# ProPrj_ChopperIA_NoBuriedBlindVias.net
KiCad netlist of a schematic drawn in EasyEDA Pro
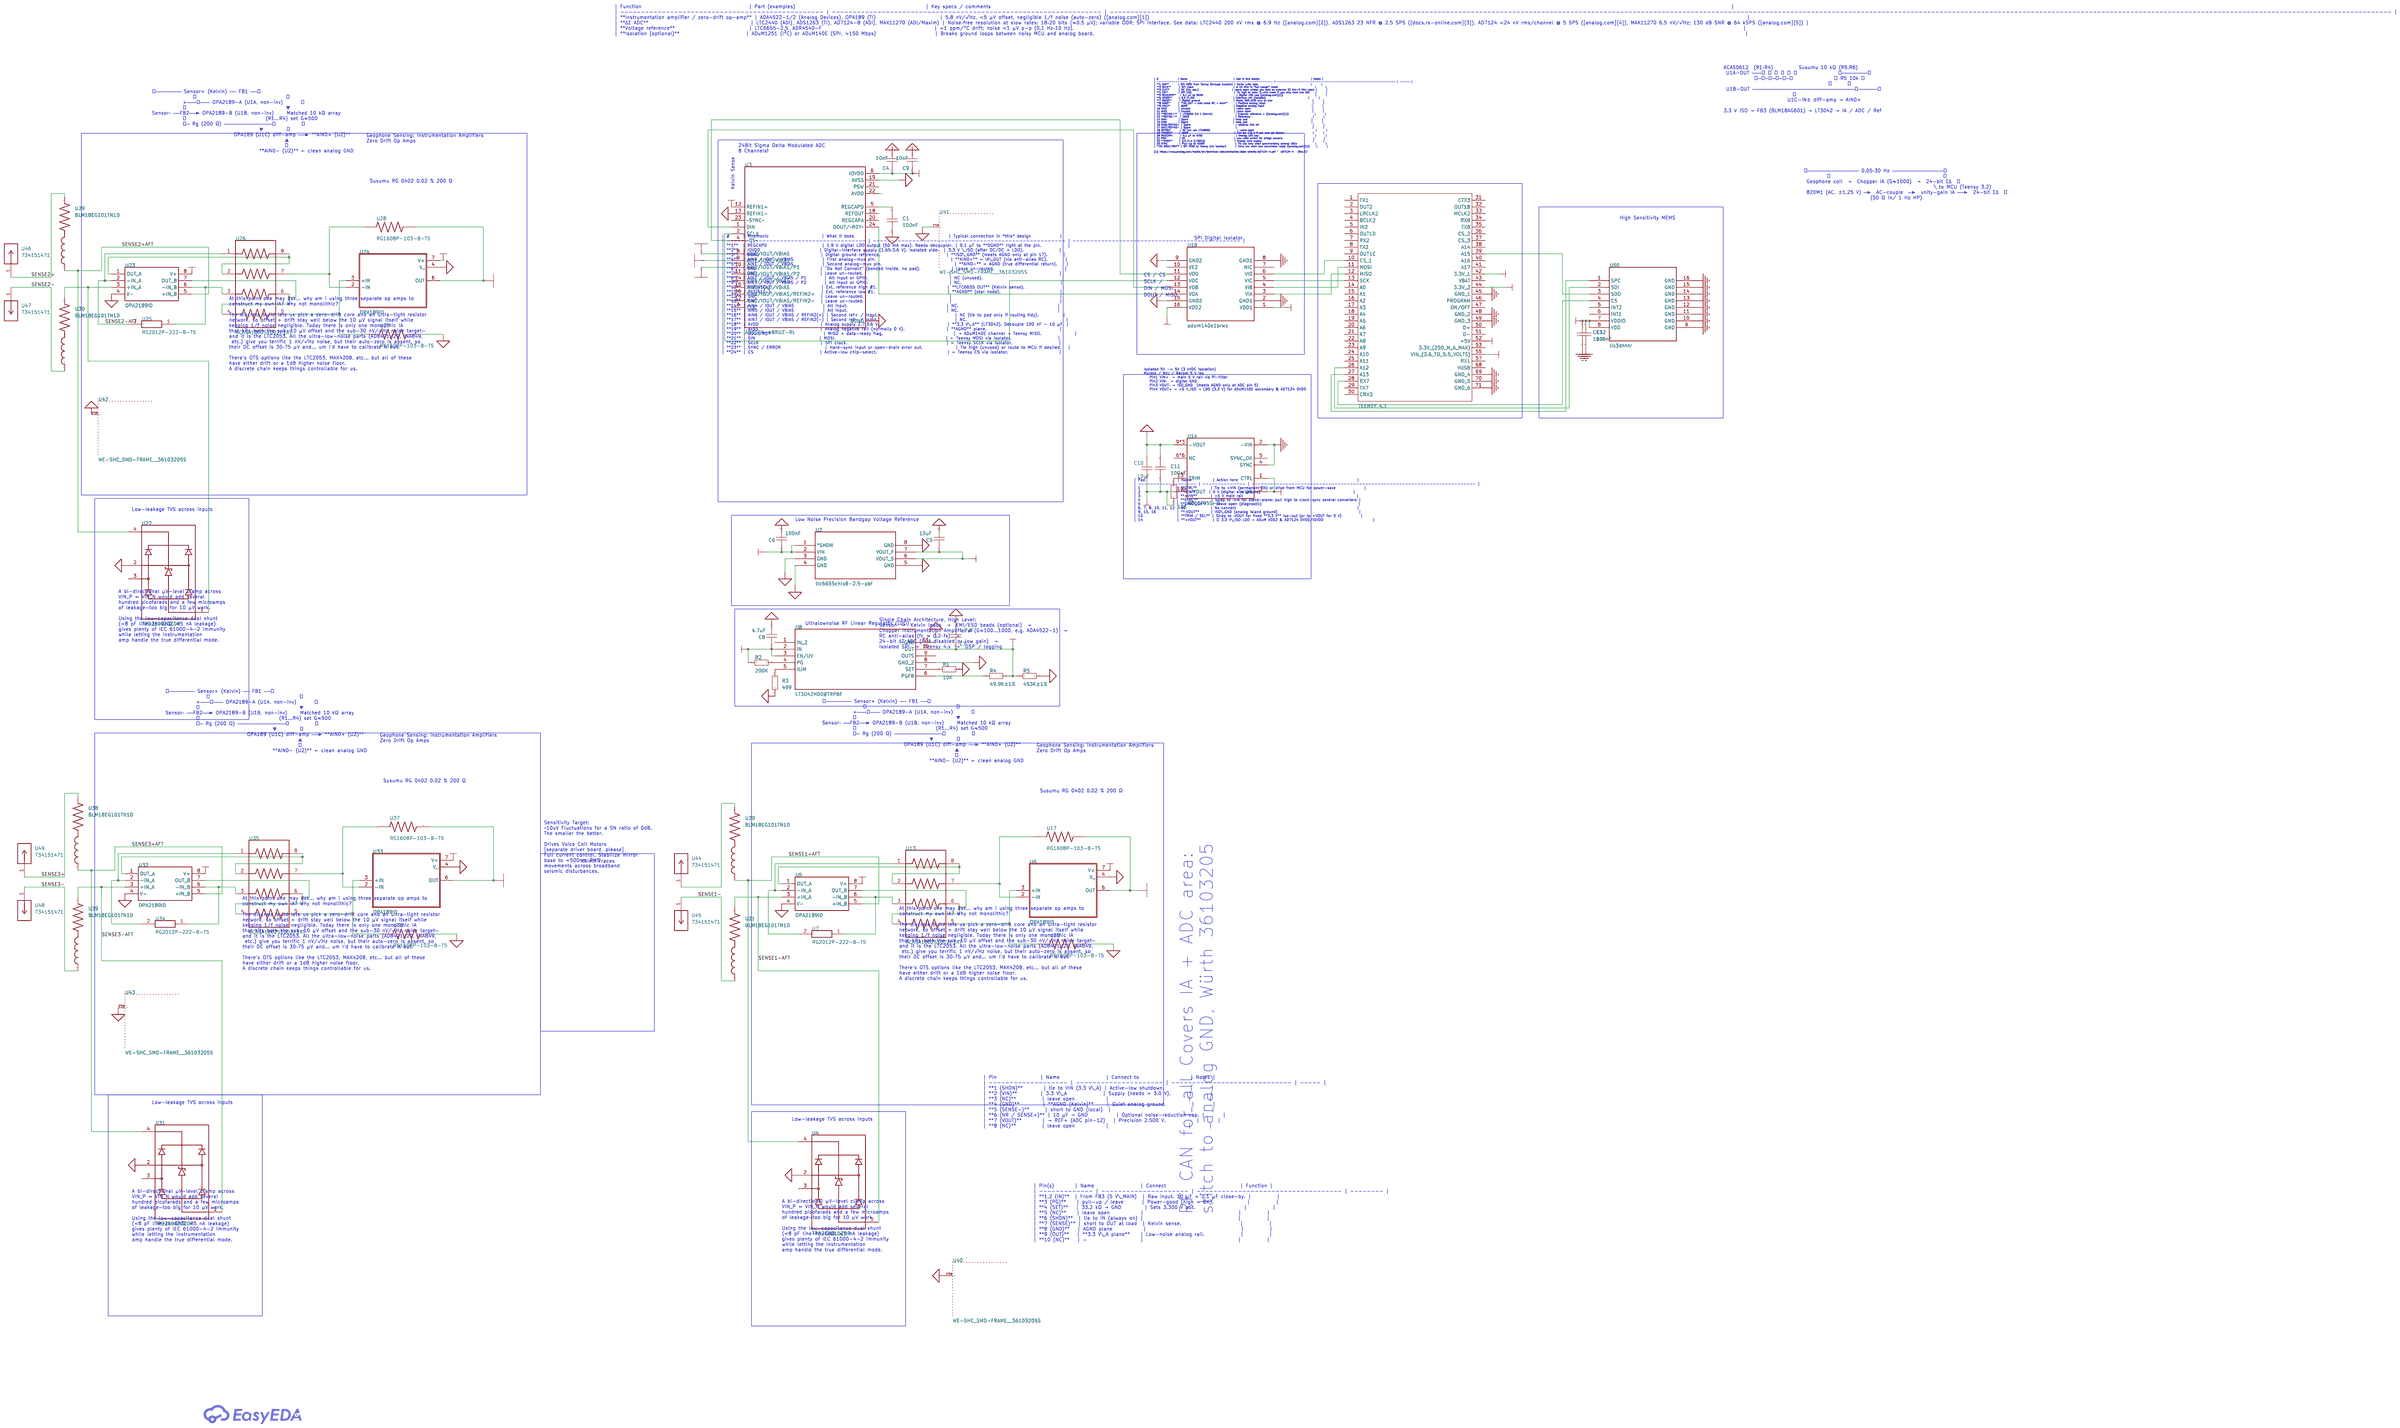
[diagram p0: schematic sheet]

(export (version "E")
  (design (tool "Eeschema 10.0.6"))
  (components
    (comp (ref "C1")
      (value "100nF")
      (footprint "easyedapro:C0603")
      (libsource (lib "easyedapro") (part "CapAcitance"))
    )
    (comp (ref "C4")
      (value "10nF")
      (footprint "easyedapro:C0603")
      (libsource (lib "easyedapro") (part "CapAcitance"))
    )
    (comp (ref "C5")
      (value "10uF")
      (footprint "easyedapro:C0603")
      (libsource (lib "easyedapro") (part "CapAcitance"))
    )
    (comp (ref "C6")
      (value "100nF")
      (footprint "easyedapro:C0603")
      (libsource (lib "easyedapro") (part "CapAcitance"))
    )
    (comp (ref "C7")
      (value "4.7uF")
      (footprint "easyedapro:C0603")
      (libsource (lib "easyedapro") (part "CapAcitance"))
    )
    (comp (ref "C8")
      (value "4.7uF")
      (footprint "easyedapro:C0603")
      (libsource (lib "easyedapro") (part "CapAcitance"))
    )
    (comp (ref "C9")
      (value "10nF")
      (footprint "easyedapro:C0603")
      (libsource (lib "easyedapro") (part "CapAcitance"))
    )
    (comp (ref "C10")
      (value "10uF")
      (footprint "easyedapro:C0603")
      (libsource (lib "easyedapro") (part "CapAcitance"))
    )
    (comp (ref "C11")
      (value "100nF")
      (footprint "easyedapro:C0603")
      (libsource (lib "easyedapro") (part "CapAcitance"))
    )
    (comp (ref "C12")
      (value "100nF")
      (footprint "easyedapro:C0603")
      (libsource (lib "easyedapro") (part "CapAcitance"))
    )
    (comp (ref "C13")
      (value "10uF")
      (footprint "easyedapro:C0603")
      (libsource (lib "easyedapro") (part "CapAcitance"))
    )
    (comp (ref "R1") (value "10K") (footprint "easyedapro:R0603") (libsource (lib "easyedapro") (part "电阻")))
    (comp (ref "R2") (value "200K") (footprint "easyedapro:R0603") (libsource (lib "easyedapro") (part "电阻")))
    (comp (ref "R3") (value "499") (footprint "easyedapro:R0603") (libsource (lib "easyedapro") (part "电阻")))
    (comp (ref "R4")
      (value "49.9K±1%")
      (footprint "easyedapro:R0603")
      (libsource (lib "easyedapro") (part "电阻"))
    )
    (comp (ref "R5")
      (value "453K±1%")
      (footprint "easyedapro:R0603")
      (libsource (lib "easyedapro") (part "电阻"))
    )
    (comp (ref "R6") (value "10K") (footprint "easyedapro:R0603") (libsource (lib "easyedapro") (part "电阻")))
    (comp (ref "U2")
      (value "ltc6655chls8-2.5-pbf")
      (footprint "easyedapro:LTC6655CHLS8-2.5-PBF")
      (libsource (lib "easyedapro") (part "ltc6655chls8-2.5-pbf"))
    )
    (comp (ref "U3")
      (value "AD7124-4BRUZ-RL")
      (footprint "easyedapro:SOP65P640X120-24N")
      (libsource (lib "easyedapro") (part "AD7124-4BRUZ-RL"))
    )
    (comp (ref "U4")
      (value "TPD2E001DZDR")
      (footprint "easyedapro:SOT192P237X122-4N")
      (libsource (lib "easyedapro") (part "TPD2E001DZDR"))
    )
    (comp (ref "U5")
      (value "OPA2189ID")
      (footprint "easyedapro:SOIC127P600X175-8N")
      (description "2 Op Amps in 1. Zero Drift.")
      (libsource (lib "easyedapro") (part "OPA2189ID"))
    )
    (comp (ref "U6")
      (value "OPA189ID")
      (footprint "easyedapro:SOIC127P599X175-8N")
      (libsource (lib "easyedapro") (part "OPA189ID"))
    )
    (comp (ref "U7")
      (value "RG2012P-222-B-T5")
      (footprint "easyedapro:RESC2012X50N")
      (libsource (lib "easyedapro") (part "RG2012P-222-B-T5"))
    )
    (comp (ref "U8")
      (value "LT3042HDD#TRPBF")
      (footprint "easyedapro:DFN-10_DD")
      (description "LDO")
      (libsource (lib "easyedapro") (part "LT3042HDD#TRPBF"))
    )
    (comp (ref "U13")
      (value "ACASA1002S1002P1AT")
      (footprint "easyedapro:RESCAXS80P320X150X55-8N")
      (libsource (lib "easyedapro") (part "ACASA1002S1002P1AT"))
    )
    (comp (ref "U14")
      (value "R05CT05S-R")
      (footprint "easyedapro:SOIC127P1030X265-16N")
      (description "Isolated 5 V→5 V DC/DC")
      (libsource (lib "easyedapro") (part "R05CT05S-R"))
    )
    (comp (ref "U16")
      (value "RG1608P-103-B-T5")
      (footprint "easyedapro:RESC1608X50N")
      (libsource (lib "easyedapro") (part "RG1608P-103-B-T5"))
    )
    (comp (ref "U17")
      (value "RG1608P-103-B-T5")
      (footprint "easyedapro:RESC1608X50N")
      (libsource (lib "easyedapro") (part "RG1608P-103-B-T5"))
    )
    (comp (ref "U18")
      (value "adum140e1brwz")
      (footprint "easyedapro:ADUM140E1BRWZ")
      (libsource (lib "easyedapro") (part "adum140e1brwz"))
    )
    (comp (ref "U20")
      (value "BLM18EG101TN1D")
      (footprint "easyedapro:BEADC1608X65N")
      (description "Ferrite Bead")
      (libsource (lib "easyedapro") (part "BLM18EG101TN1D"))
    )
    (comp (ref "U21")
      (value "BLM18EG101TN1D")
      (footprint "easyedapro:BEADC1608X65N")
      (description "Ferrite Bead")
      (libsource (lib "easyedapro") (part "BLM18EG101TN1D"))
    )
    (comp (ref "U22")
      (value "TPD2E001DZDR")
      (footprint "easyedapro:SOT192P237X122-4N")
      (libsource (lib "easyedapro") (part "TPD2E001DZDR"))
    )
    (comp (ref "U23")
      (value "OPA2189ID")
      (footprint "easyedapro:SOIC127P600X175-8N")
      (description "2 Op Amps in 1. Zero Drift.")
      (libsource (lib "easyedapro") (part "OPA2189ID"))
    )
    (comp (ref "U24")
      (value "OPA189ID")
      (footprint "easyedapro:SOIC127P599X175-8N")
      (libsource (lib "easyedapro") (part "OPA189ID"))
    )
    (comp (ref "U25")
      (value "RG2012P-222-B-T5")
      (footprint "easyedapro:RESC2012X50N")
      (libsource (lib "easyedapro") (part "RG2012P-222-B-T5"))
    )
    (comp (ref "U26")
      (value "ACASA1002S1002P1AT")
      (footprint "easyedapro:RESCAXS80P320X150X55-8N")
      (libsource (lib "easyedapro") (part "ACASA1002S1002P1AT"))
    )
    (comp (ref "U27")
      (value "RG1608P-103-B-T5")
      (footprint "easyedapro:RESC1608X50N")
      (libsource (lib "easyedapro") (part "RG1608P-103-B-T5"))
    )
    (comp (ref "U28")
      (value "RG1608P-103-B-T5")
      (footprint "easyedapro:RESC1608X50N")
      (libsource (lib "easyedapro") (part "RG1608P-103-B-T5"))
    )
    (comp (ref "U29")
      (value "BLM18EG101TN1D")
      (footprint "easyedapro:BEADC1608X65N")
      (description "Ferrite Bead")
      (libsource (lib "easyedapro") (part "BLM18EG101TN1D"))
    )
    (comp (ref "U30")
      (value "BLM18EG101TN1D")
      (footprint "easyedapro:BEADC1608X65N")
      (description "Ferrite Bead")
      (libsource (lib "easyedapro") (part "BLM18EG101TN1D"))
    )
    (comp (ref "U31")
      (value "TPD2E001DZDR")
      (footprint "easyedapro:SOT192P237X122-4N")
      (libsource (lib "easyedapro") (part "TPD2E001DZDR"))
    )
    (comp (ref "U32")
      (value "OPA2189ID")
      (footprint "easyedapro:SOIC127P600X175-8N")
      (description "2 Op Amps in 1. Zero Drift.")
      (libsource (lib "easyedapro") (part "OPA2189ID"))
    )
    (comp (ref "U33")
      (value "OPA189ID")
      (footprint "easyedapro:SOIC127P599X175-8N")
      (libsource (lib "easyedapro") (part "OPA189ID"))
    )
    (comp (ref "U34")
      (value "RG2012P-222-B-T5")
      (footprint "easyedapro:RESC2012X50N")
      (libsource (lib "easyedapro") (part "RG2012P-222-B-T5"))
    )
    (comp (ref "U35")
      (value "ACASA1002S1002P1AT")
      (footprint "easyedapro:RESCAXS80P320X150X55-8N")
      (libsource (lib "easyedapro") (part "ACASA1002S1002P1AT"))
    )
    (comp (ref "U36")
      (value "RG1608P-103-B-T5")
      (footprint "easyedapro:RESC1608X50N")
      (libsource (lib "easyedapro") (part "RG1608P-103-B-T5"))
    )
    (comp (ref "U37")
      (value "RG1608P-103-B-T5")
      (footprint "easyedapro:RESC1608X50N")
      (libsource (lib "easyedapro") (part "RG1608P-103-B-T5"))
    )
    (comp (ref "U38")
      (value "BLM18EG101TN1D")
      (footprint "easyedapro:BEADC1608X65N")
      (description "Ferrite Bead")
      (libsource (lib "easyedapro") (part "BLM18EG101TN1D"))
    )
    (comp (ref "U39")
      (value "BLM18EG101TN1D")
      (footprint "easyedapro:BEADC1608X65N")
      (description "Ferrite Bead")
      (libsource (lib "easyedapro") (part "BLM18EG101TN1D"))
    )
    (comp (ref "U40")
      (value "WE-SHC_SMD-FRAME__36103205S")
      (footprint "easyedapro:WE-SHC_SMD-FRAME_36103205S")
      (libsource (lib "easyedapro") (part "WE-SHC_SMD-FRAME__36103205S"))
    )
    (comp (ref "U41")
      (value "WE-SHC_SMD-FRAME__36103205S")
      (footprint "easyedapro:WE-SHC_SMD-FRAME_36103205S")
      (libsource (lib "easyedapro") (part "WE-SHC_SMD-FRAME__36103205S"))
    )
    (comp (ref "U42")
      (value "WE-SHC_SMD-FRAME__36103205S")
      (footprint "easyedapro:WE-SHC_SMD-FRAME_36103205S")
      (libsource (lib "easyedapro") (part "WE-SHC_SMD-FRAME__36103205S"))
    )
    (comp (ref "U43")
      (value "WE-SHC_SMD-FRAME__36103205S")
      (footprint "easyedapro:WE-SHC_SMD-FRAME_36103205S")
      (libsource (lib "easyedapro") (part "WE-SHC_SMD-FRAME__36103205S"))
    )
    (comp (ref "U44")
      (value "734151471")
      (footprint "easyedapro:CONN_734151471_MOL")
      (libsource (lib "easyedapro") (part "734151471"))
    )
    (comp (ref "U45")
      (value "734151471")
      (footprint "easyedapro:CONN_734151471_MOL")
      (libsource (lib "easyedapro") (part "734151471"))
    )
    (comp (ref "U46")
      (value "734151471")
      (footprint "easyedapro:CONN_734151471_MOL")
      (libsource (lib "easyedapro") (part "734151471"))
    )
    (comp (ref "U47")
      (value "734151471")
      (footprint "easyedapro:CONN_734151471_MOL")
      (libsource (lib "easyedapro") (part "734151471"))
    )
    (comp (ref "U48")
      (value "734151471")
      (footprint "easyedapro:CONN_734151471_MOL")
      (libsource (lib "easyedapro") (part "734151471"))
    )
    (comp (ref "U49")
      (value "734151471")
      (footprint "easyedapro:CONN_734151471_MOL")
      (libsource (lib "easyedapro") (part "734151471"))
    )
    (comp (ref "U50")
      (value "lis3dhhtr")
      (footprint "easyedapro:LIS3DHHTR")
      (libsource (lib "easyedapro") (part "lis3dhhtr"))
    )
    (comp (ref "U51")
      (value "TEENSY_4.1")
      (footprint "easyedapro:TEENSY41")
      (libsource (lib "easyedapro") (part "TEENSY_4.1"))
    )
  )
  (nets
    (net (code "1") (name "+2.5V") (class "Default")
      (node (ref "C5") (pin "2") (pinfunction "2_2") (pintype "input"))
      (node (ref "U2") (pin "6") (pinfunction "VOUT_S_6") (pintype "unspecified"))
      (node (ref "U2") (pin "7") (pinfunction "VOUT_F_7") (pintype "unspecified"))
      (node (ref "U3") (pin "12") (pinfunction "REFIN1+_12") (pintype "input"))
    )
    (net (code "2") (name "+3.3VANALOGSIDE") (class "Default")
      (node (ref "C4") (pin "1") (pinfunction "1_1") (pintype "input"))
      (node (ref "C6") (pin "2") (pinfunction "2_2") (pintype "input"))
      (node (ref "C7") (pin "2") (pinfunction "2_2") (pintype "input"))
      (node (ref "C9") (pin "1") (pinfunction "1_1") (pintype "input"))
      (node (ref "R4") (pin "2") (pinfunction "2_2") (pintype "input"))
      (node (ref "R5") (pin "1") (pinfunction "1_1") (pintype "input"))
      (node (ref "U18") (pin "16") (pinfunction "VDD2_16") (pintype "unspecified"))
      (node (ref "U2") (pin "1") (pinfunction "*SHDN_1") (pintype "unspecified"))
      (node (ref "U2") (pin "2") (pinfunction "VIN_2") (pintype "unspecified"))
      (node (ref "U23") (pin "8") (pinfunction "V+_8") (pintype "bidirectional"))
      (node (ref "U24") (pin "7") (pinfunction "V+_7") (pintype "unspecified"))
      (node (ref "U3") (pin "6") (pinfunction "IOVDD_6") (pintype "unspecified"))
      (node (ref "U32") (pin "8") (pinfunction "V+_8") (pintype "bidirectional"))
      (node (ref "U33") (pin "7") (pinfunction "V+_7") (pintype "unspecified"))
      (node (ref "U5") (pin "8") (pinfunction "V+_8") (pintype "bidirectional"))
      (node (ref "U6") (pin "7") (pinfunction "V+_7") (pintype "unspecified"))
      (node (ref "U8") (pin "10") (pinfunction "OUT_10") (pintype "output"))
    )
    (net (code "3") (name "+3.3V_D") (class "Default")
      (node (ref "C12") (pin "2") (pinfunction "2_2") (pintype "input"))
      (node (ref "C13") (pin "2") (pinfunction "2_2") (pintype "input"))
      (node (ref "U18") (pin "1") (pinfunction "VDD1_1") (pintype "unspecified"))
      (node (ref "U50") (pin "7") (pinfunction "VDDIO_7") (pintype "unspecified"))
      (node (ref "U50") (pin "8") (pinfunction "VDD_8") (pintype "unspecified"))
      (node (ref "U51") (pin "42") (pinfunction "3.3V_1_42") (pintype "bidirectional"))
      (node (ref "U51") (pin "44") (pinfunction "3.3V_2_44") (pintype "bidirectional"))
    )
    (net (code "4") (name "+5V_D") (class "Default")
      (node (ref "U14") (pin "1") (pinfunction "CTRL_1") (pintype "input"))
      (node (ref "U14") (pin "3") (pinfunction "+VIN_3") (pintype "input"))
      (node (ref "U51") (pin "52") (pinfunction "+5V_52") (pintype "bidirectional"))
      (node (ref "U51") (pin "55") (pinfunction "VIN_(3.6_TO_5.5_VOLTS)_55") (pintype "bidirectional"))
    )
    (net (code "5") (name "+5V_ISO") (class "Default")
      (node (ref "C10") (pin "1") (pinfunction "1_1") (pintype "input"))
      (node (ref "C11") (pin "1") (pinfunction "1_1") (pintype "input"))
      (node (ref "C8") (pin "2") (pinfunction "2_2") (pintype "input"))
      (node (ref "R2") (pin "1") (pinfunction "1_1") (pintype "input"))
      (node (ref "R6") (pin "1") (pinfunction "1_1") (pintype "input"))
      (node (ref "U14") (pin "14") (pinfunction "+VOUT_14") (pintype "output"))
      (node (ref "U8") (pin "2") (pinfunction "IN_2") (pintype "input"))
      (node (ref "U8") (pin "3") (pinfunction "EN/UV_3") (pintype "output"))
    )
    (net (code "6") (name "/SENSE1+AFT") (class "Default")
      (node (ref "U20") (pin "1") (pinfunction "1_1") (pintype "unspecified"))
      (node (ref "U4") (pin "4") (pinfunction "VCC_4") (pintype "unspecified"))
      (node (ref "U5") (pin "5") (pinfunction "+IN_B_5") (pintype "bidirectional"))
    )
    (net (code "7") (name "/SENSE1-") (class "Default")
      (node (ref "U21") (pin "1") (pinfunction "1_1") (pintype "unspecified"))
      (node (ref "U45") (pin "1") (pinfunction "1_1") (pintype "unspecified"))
    )
    (net (code "8") (name "/SENSE1-AFT") (class "Default")
      (node (ref "U21") (pin "2") (pinfunction "2_2") (pintype "unspecified"))
      (node (ref "U4") (pin "1") (pinfunction "GND_1") (pintype "unspecified"))
      (node (ref "U5") (pin "3") (pinfunction "+IN_A_3") (pintype "bidirectional"))
    )
    (net (code "9") (name "/SENSE2+") (class "Default")
      (node (ref "U29") (pin "2") (pinfunction "2_2") (pintype "unspecified"))
      (node (ref "U46") (pin "1") (pinfunction "1_1") (pintype "unspecified"))
    )
    (net (code "10") (name "/SENSE2+AFT") (class "Default")
      (node (ref "U22") (pin "4") (pinfunction "VCC_4") (pintype "unspecified"))
      (node (ref "U23") (pin "5") (pinfunction "+IN_B_5") (pintype "bidirectional"))
      (node (ref "U29") (pin "1") (pinfunction "1_1") (pintype "unspecified"))
    )
    (net (code "11") (name "/SENSE2-") (class "Default")
      (node (ref "U30") (pin "1") (pinfunction "1_1") (pintype "unspecified"))
      (node (ref "U47") (pin "1") (pinfunction "1_1") (pintype "unspecified"))
    )
    (net (code "12") (name "/SENSE2-AFT") (class "Default")
      (node (ref "U23") (pin "2") (pinfunction "-IN_A_2") (pintype "bidirectional"))
      (node (ref "U25") (pin "2") (pinfunction "2_2") (pintype "bidirectional"))
      (node (ref "U26") (pin "1") (pinfunction "1_1") (pintype "unspecified"))
    )
    (net (code "13") (name "/SENSE3+") (class "Default")
      (node (ref "U38") (pin "2") (pinfunction "2_2") (pintype "unspecified"))
      (node (ref "U49") (pin "1") (pinfunction "1_1") (pintype "unspecified"))
    )
    (net (code "14") (name "/SENSE3+AFT") (class "Default")
      (node (ref "U31") (pin "4") (pinfunction "VCC_4") (pintype "unspecified"))
      (node (ref "U32") (pin "5") (pinfunction "+IN_B_5") (pintype "bidirectional"))
      (node (ref "U38") (pin "1") (pinfunction "1_1") (pintype "unspecified"))
    )
    (net (code "15") (name "/SENSE3-") (class "Default")
      (node (ref "U39") (pin "1") (pinfunction "1_1") (pintype "unspecified"))
      (node (ref "U48") (pin "1") (pinfunction "1_1") (pintype "unspecified"))
    )
    (net (code "16") (name "/SENSE3-AFT") (class "Default")
      (node (ref "U31") (pin "1") (pinfunction "GND_1") (pintype "unspecified"))
      (node (ref "U32") (pin "3") (pinfunction "+IN_A_3") (pintype "bidirectional"))
      (node (ref "U39") (pin "2") (pinfunction "2_2") (pintype "unspecified"))
    )
    (net (code "17") (name "AGND") (class "Default")
      (node (ref "C1") (pin "2") (pinfunction "2_2") (pintype "input"))
      (node (ref "C10") (pin "2") (pinfunction "2_2") (pintype "input"))
      (node (ref "C11") (pin "2") (pinfunction "2_2") (pintype "input"))
      (node (ref "C4") (pin "2") (pinfunction "2_2") (pintype "input"))
      (node (ref "C5") (pin "1") (pinfunction "1_1") (pintype "input"))
      (node (ref "C6") (pin "1") (pinfunction "1_1") (pintype "input"))
      (node (ref "C7") (pin "1") (pinfunction "1_1") (pintype "input"))
      (node (ref "C8") (pin "1") (pinfunction "1_1") (pintype "input"))
      (node (ref "C9") (pin "2") (pinfunction "2_2") (pintype "input"))
      (node (ref "R1") (pin "2") (pinfunction "2_2") (pintype "input"))
      (node (ref "R3") (pin "1") (pinfunction "1_1") (pintype "input"))
      (node (ref "R5") (pin "2") (pinfunction "2_2") (pintype "input"))
      (node (ref "U14") (pin "9*3") (pinfunction "-VOUT_9*3") (pintype "output"))
      (node (ref "U16") (pin "2") (pinfunction "2_2") (pintype "unspecified"))
      (node (ref "U18") (pin "15") (pinfunction "GND2_15") (pintype "unspecified"))
      (node (ref "U18") (pin "9") (pinfunction "GND2_9") (pintype "unspecified"))
      (node (ref "U2") (pin "3") (pinfunction "GND_3") (pintype "unspecified"))
      (node (ref "U2") (pin "4") (pinfunction "GND_4") (pintype "unspecified"))
      (node (ref "U2") (pin "5") (pinfunction "GND_5") (pintype "unspecified"))
      (node (ref "U2") (pin "8") (pinfunction "GND_8") (pintype "unspecified"))
      (node (ref "U22") (pin "2") (pinfunction "IO1_2") (pintype "bidirectional"))
      (node (ref "U23") (pin "4") (pinfunction "V-_4") (pintype "bidirectional"))
      (node (ref "U24") (pin "4") (pinfunction "V__4") (pintype "unspecified"))
      (node (ref "U27") (pin "2") (pinfunction "2_2") (pintype "unspecified"))
      (node (ref "U3") (pin "13") (pinfunction "REFIN1-_13") (pintype "input"))
      (node (ref "U3") (pin "19") (pinfunction "AVSS_19") (pintype "unspecified"))
      (node (ref "U3") (pin "7") (pinfunction "DGND_7") (pintype "unspecified"))
      (node (ref "U31") (pin "2") (pinfunction "IO1_2") (pintype "bidirectional"))
      (node (ref "U32") (pin "4") (pinfunction "V-_4") (pintype "bidirectional"))
      (node (ref "U33") (pin "4") (pinfunction "V__4") (pintype "unspecified"))
      (node (ref "U36") (pin "2") (pinfunction "2_2") (pintype "unspecified"))
      (node (ref "U4") (pin "2") (pinfunction "IO1_2") (pintype "bidirectional"))
      (node (ref "U40") (pin "1*16") (pinfunction "GND_1*16") (pintype "unspecified"))
      (node (ref "U41") (pin "1*16") (pinfunction "GND_1*16") (pintype "unspecified"))
      (node (ref "U42") (pin "1*16") (pinfunction "GND_1*16") (pintype "unspecified"))
      (node (ref "U43") (pin "1*16") (pinfunction "GND_1*16") (pintype "unspecified"))
      (node (ref "U5") (pin "4") (pinfunction "V-_4") (pintype "bidirectional"))
      (node (ref "U6") (pin "4") (pinfunction "V__4") (pintype "unspecified"))
      (node (ref "U8") (pin "11") (pinfunction "GND_11") (pintype "unspecified"))
      (node (ref "U8") (pin "8") (pinfunction "GND_2_8") (pintype "unspecified"))
    )
    (net (code "18") (name "DGND") (class "Default")
      (node (ref "C12") (pin "1") (pinfunction "1_1") (pintype "input"))
      (node (ref "C13") (pin "1") (pinfunction "1_1") (pintype "input"))
      (node (ref "U14") (pin "2") (pinfunction "-VIN_2") (pintype "input"))
      (node (ref "U14") (pin "4") (pinfunction "SYNC_4") (pintype "input"))
      (node (ref "U18") (pin "2") (pinfunction "GND1_2") (pintype "unspecified"))
      (node (ref "U18") (pin "8") (pinfunction "GND1_8") (pintype "unspecified"))
      (node (ref "U50") (pin "10") (pinfunction "GND_10") (pintype "unspecified"))
      (node (ref "U50") (pin "11") (pinfunction "GND_11") (pintype "unspecified"))
      (node (ref "U50") (pin "12") (pinfunction "GND_12") (pintype "unspecified"))
      (node (ref "U50") (pin "13") (pinfunction "GND_13") (pintype "unspecified"))
      (node (ref "U50") (pin "14") (pinfunction "GND_14") (pintype "unspecified"))
      (node (ref "U50") (pin "15") (pinfunction "GND_15") (pintype "unspecified"))
      (node (ref "U50") (pin "16") (pinfunction "GND_16") (pintype "unspecified"))
      (node (ref "U50") (pin "9") (pinfunction "GND_9") (pintype "unspecified"))
      (node (ref "U51") (pin "45") (pinfunction "GND_1_45") (pintype "bidirectional"))
      (node (ref "U51") (pin "48") (pinfunction "GND_2_48") (pintype "bidirectional"))
      (node (ref "U51") (pin "49") (pinfunction "GND_3_49") (pintype "bidirectional"))
      (node (ref "U51") (pin "69") (pinfunction "GND_4_69") (pintype "bidirectional"))
      (node (ref "U51") (pin "70") (pinfunction "GND_5_70") (pintype "bidirectional"))
      (node (ref "U51") (pin "71") (pinfunction "GND_6_71") (pintype "bidirectional"))
    )
    (net (code "19") (name "Net-(U3-REGCAPD)") (class "Default")
      (node (ref "C1") (pin "1") (pinfunction "1_1") (pintype "input"))
      (node (ref "U3") (pin "5") (pinfunction "REGCAPD_5") (pintype "output"))
    )
    (net (code "20") (name "Net-(U5--IN_A)") (class "Default")
      (node (ref "U13") (pin "1") (pinfunction "1_1") (pintype "unspecified"))
      (node (ref "U5") (pin "2") (pinfunction "-IN_A_2") (pintype "bidirectional"))
      (node (ref "U7") (pin "2") (pinfunction "2_2") (pintype "bidirectional"))
    )
    (net (code "21") (name "Net-(U5--IN_B)") (class "Default")
      (node (ref "U13") (pin "3") (pinfunction "3_3") (pintype "unspecified"))
      (node (ref "U5") (pin "6") (pinfunction "-IN_B_6") (pintype "bidirectional"))
      (node (ref "U7") (pin "1") (pinfunction "1_1") (pintype "bidirectional"))
    )
    (net (code "22") (name "Net-(U5-OUT_A)") (class "Default")
      (node (ref "U13") (pin "2") (pinfunction "2_2") (pintype "unspecified"))
      (node (ref "U13") (pin "8") (pinfunction "8_8") (pintype "unspecified"))
      (node (ref "U5") (pin "1") (pinfunction "OUT_A_1") (pintype "bidirectional"))
    )
    (net (code "23") (name "Net-(U5-OUT_B)") (class "Default")
      (node (ref "U13") (pin "4") (pinfunction "4_4") (pintype "unspecified"))
      (node (ref "U13") (pin "6") (pinfunction "6_6") (pintype "unspecified"))
      (node (ref "U5") (pin "7") (pinfunction "OUT_B_7") (pintype "bidirectional"))
    )
    (net (code "24") (name "Net-(U6-+IN)") (class "Default")
      (node (ref "U13") (pin "5") (pinfunction "5_5") (pintype "unspecified"))
      (node (ref "U16") (pin "1") (pinfunction "1_1") (pintype "unspecified"))
      (node (ref "U6") (pin "3") (pinfunction "+IN_3") (pintype "input"))
    )
    (net (code "25") (name "Net-(U6--IN)") (class "Default")
      (node (ref "U13") (pin "7") (pinfunction "7_7") (pintype "unspecified"))
      (node (ref "U17") (pin "1") (pinfunction "1_1") (pintype "unspecified"))
      (node (ref "U6") (pin "2") (pinfunction "-IN_2") (pintype "input"))
    )
    (net (code "26") (name "Net-(U8-ILIM)") (class "Default")
      (node (ref "R3") (pin "2") (pinfunction "2_2") (pintype "input"))
      (node (ref "U8") (pin "5") (pinfunction "ILIM_5") (pintype "unspecified"))
    )
    (net (code "27") (name "Net-(U8-PG)") (class "Default")
      (node (ref "R2") (pin "2") (pinfunction "2_2") (pintype "input"))
      (node (ref "U8") (pin "4") (pinfunction "PG_4") (pintype "unspecified"))
    )
    (net (code "28") (name "Net-(U8-PGFB)") (class "Default")
      (node (ref "R4") (pin "1") (pinfunction "1_1") (pintype "input"))
      (node (ref "U8") (pin "6") (pinfunction "PGFB_6") (pintype "unspecified"))
    )
    (net (code "29") (name "Net-(U8-SET)") (class "Default")
      (node (ref "R1") (pin "1") (pinfunction "1_1") (pintype "input"))
      (node (ref "U8") (pin "7") (pinfunction "SET_7") (pintype "input"))
    )
    (net (code "30") (name "Net-(U14-TRIM)") (class "Default")
      (node (ref "R6") (pin "2") (pinfunction "2_2") (pintype "input"))
      (node (ref "U14") (pin "13") (pinfunction "TRIM_13") (pintype "unspecified"))
    )
    (net (code "31") (name "Net-(U18-VIA)") (class "Default")
      (node (ref "U18") (pin "3") (pinfunction "VIA_3") (pintype "unspecified"))
      (node (ref "U51") (pin "12") (pinfunction "MISO_12") (pintype "bidirectional"))
    )
    (net (code "32") (name "Net-(U18-VIB)") (class "Default")
      (node (ref "U18") (pin "4") (pinfunction "VIB_4") (pintype "unspecified"))
      (node (ref "U51") (pin "11") (pinfunction "MOSI_11") (pintype "bidirectional"))
    )
    (net (code "33") (name "Net-(U18-VIC)") (class "Default")
      (node (ref "U18") (pin "5") (pinfunction "VIC_5") (pintype "unspecified"))
      (node (ref "U51") (pin "13") (pinfunction "SCK_13") (pintype "bidirectional"))
    )
    (net (code "34") (name "Net-(U18-VID)") (class "Default")
      (node (ref "U18") (pin "6") (pinfunction "VID_6") (pintype "unspecified"))
      (node (ref "U51") (pin "10") (pinfunction "CS_1_10") (pintype "bidirectional"))
    )
    (net (code "35") (name "Net-(U18-VOA)") (class "Default")
      (node (ref "U18") (pin "14") (pinfunction "VOA_14") (pintype "unspecified"))
      (node (ref "U3") (pin "24") (pinfunction "DOUT/~RDY~_24") (pintype "output"))
    )
    (net (code "36") (name "Net-(U18-VOB)") (class "Default")
      (node (ref "U18") (pin "13") (pinfunction "VOB_13") (pintype "unspecified"))
      (node (ref "U3") (pin "1") (pinfunction "DIN_1") (pintype "input"))
    )
    (net (code "37") (name "Net-(U18-VOC)") (class "Default")
      (node (ref "U18") (pin "12") (pinfunction "VOC_12") (pintype "unspecified"))
      (node (ref "U3") (pin "2") (pinfunction "SCLK_2") (pintype "input"))
    )
    (net (code "38") (name "Net-(U18-VOD)") (class "Default")
      (node (ref "U18") (pin "11") (pinfunction "VOD_11") (pintype "unspecified"))
      (node (ref "U3") (pin "4") (pinfunction "~CS~_4") (pintype "input"))
    )
    (net (code "39") (name "Net-(U20-Pad2)") (class "Default")
      (node (ref "U20") (pin "2") (pinfunction "2_2") (pintype "unspecified"))
      (node (ref "U44") (pin "1") (pinfunction "1_1") (pintype "unspecified"))
    )
    (net (code "40") (name "Net-(U22-GND)") (class "Default")
      (node (ref "U22") (pin "1") (pinfunction "GND_1") (pintype "unspecified"))
      (node (ref "U23") (pin "3") (pinfunction "+IN_A_3") (pintype "bidirectional"))
      (node (ref "U30") (pin "2") (pinfunction "2_2") (pintype "unspecified"))
    )
    (net (code "41") (name "Net-(U23--IN_B)") (class "Default")
      (node (ref "U23") (pin "6") (pinfunction "-IN_B_6") (pintype "bidirectional"))
      (node (ref "U25") (pin "1") (pinfunction "1_1") (pintype "bidirectional"))
      (node (ref "U26") (pin "3") (pinfunction "3_3") (pintype "unspecified"))
    )
    (net (code "42") (name "Net-(U23-OUT_A)") (class "Default")
      (node (ref "U23") (pin "1") (pinfunction "OUT_A_1") (pintype "bidirectional"))
      (node (ref "U26") (pin "2") (pinfunction "2_2") (pintype "unspecified"))
      (node (ref "U26") (pin "8") (pinfunction "8_8") (pintype "unspecified"))
    )
    (net (code "43") (name "Net-(U23-OUT_B)") (class "Default")
      (node (ref "U23") (pin "7") (pinfunction "OUT_B_7") (pintype "bidirectional"))
      (node (ref "U26") (pin "4") (pinfunction "4_4") (pintype "unspecified"))
      (node (ref "U26") (pin "6") (pinfunction "6_6") (pintype "unspecified"))
    )
    (net (code "44") (name "Net-(U24-+IN)") (class "Default")
      (node (ref "U24") (pin "3") (pinfunction "+IN_3") (pintype "input"))
      (node (ref "U26") (pin "5") (pinfunction "5_5") (pintype "unspecified"))
      (node (ref "U27") (pin "1") (pinfunction "1_1") (pintype "unspecified"))
    )
    (net (code "45") (name "Net-(U24--IN)") (class "Default")
      (node (ref "U24") (pin "2") (pinfunction "-IN_2") (pintype "input"))
      (node (ref "U26") (pin "7") (pinfunction "7_7") (pintype "unspecified"))
      (node (ref "U28") (pin "1") (pinfunction "1_1") (pintype "unspecified"))
    )
    (net (code "46") (name "Net-(U32--IN_A)") (class "Default")
      (node (ref "U32") (pin "2") (pinfunction "-IN_A_2") (pintype "bidirectional"))
      (node (ref "U34") (pin "2") (pinfunction "2_2") (pintype "bidirectional"))
      (node (ref "U35") (pin "1") (pinfunction "1_1") (pintype "unspecified"))
    )
    (net (code "47") (name "Net-(U32--IN_B)") (class "Default")
      (node (ref "U32") (pin "6") (pinfunction "-IN_B_6") (pintype "bidirectional"))
      (node (ref "U34") (pin "1") (pinfunction "1_1") (pintype "bidirectional"))
      (node (ref "U35") (pin "3") (pinfunction "3_3") (pintype "unspecified"))
    )
    (net (code "48") (name "Net-(U32-OUT_A)") (class "Default")
      (node (ref "U32") (pin "1") (pinfunction "OUT_A_1") (pintype "bidirectional"))
      (node (ref "U35") (pin "2") (pinfunction "2_2") (pintype "unspecified"))
      (node (ref "U35") (pin "8") (pinfunction "8_8") (pintype "unspecified"))
    )
    (net (code "49") (name "Net-(U32-OUT_B)") (class "Default")
      (node (ref "U32") (pin "7") (pinfunction "OUT_B_7") (pintype "bidirectional"))
      (node (ref "U35") (pin "4") (pinfunction "4_4") (pintype "unspecified"))
      (node (ref "U35") (pin "6") (pinfunction "6_6") (pintype "unspecified"))
    )
    (net (code "50") (name "Net-(U33-+IN)") (class "Default")
      (node (ref "U33") (pin "3") (pinfunction "+IN_3") (pintype "input"))
      (node (ref "U35") (pin "5") (pinfunction "5_5") (pintype "unspecified"))
      (node (ref "U36") (pin "1") (pinfunction "1_1") (pintype "unspecified"))
    )
    (net (code "51") (name "Net-(U33--IN)") (class "Default")
      (node (ref "U33") (pin "2") (pinfunction "-IN_2") (pintype "input"))
      (node (ref "U35") (pin "7") (pinfunction "7_7") (pintype "unspecified"))
      (node (ref "U37") (pin "1") (pinfunction "1_1") (pintype "unspecified"))
    )
    (net (code "52") (name "Net-(U50-CS)") (class "Default")
      (node (ref "U50") (pin "4") (pinfunction "CS_4") (pintype "unspecified"))
      (node (ref "U51") (pin "28") (pinfunction "RX7_28") (pintype "bidirectional"))
    )
    (net (code "53") (name "Net-(U50-SDI)") (class "Default")
      (node (ref "U50") (pin "2") (pinfunction "SDI_2") (pintype "unspecified"))
      (node (ref "U51") (pin "26") (pinfunction "A12_26") (pintype "bidirectional"))
    )
    (net (code "54") (name "Net-(U50-SDO)") (class "Default")
      (node (ref "U50") (pin "3") (pinfunction "SDO_3") (pintype "unspecified"))
      (node (ref "U51") (pin "39") (pinfunction "A15_39") (pintype "bidirectional"))
    )
    (net (code "55") (name "Net-(U50-SPC)") (class "Default")
      (node (ref "U50") (pin "1") (pinfunction "SPC_1") (pintype "unspecified"))
      (node (ref "U51") (pin "27") (pinfunction "A13_27") (pintype "bidirectional"))
    )
    (net (code "56") (name "VOUT1") (class "Default")
      (node (ref "U17") (pin "2") (pinfunction "2_2") (pintype "unspecified"))
      (node (ref "U3") (pin "8") (pinfunction "AIN0/IOUT/VBIAS_8") (pintype "bidirectional"))
      (node (ref "U6") (pin "6") (pinfunction "OUT_6") (pintype "output"))
    )
    (net (code "57") (name "VOUT2") (class "Default")
      (node (ref "U24") (pin "6") (pinfunction "OUT_6") (pintype "output"))
      (node (ref "U28") (pin "2") (pinfunction "2_2") (pintype "unspecified"))
      (node (ref "U3") (pin "9") (pinfunction "AIN1/IOUT/VBIAS_9") (pintype "bidirectional"))
    )
    (net (code "58") (name "VOUT3") (class "Default")
      (node (ref "U3") (pin "10") (pinfunction "AIN2/IOUT/VBIAS/P1_10") (pintype "bidirectional"))
      (node (ref "U33") (pin "6") (pinfunction "OUT_6") (pintype "output"))
      (node (ref "U37") (pin "2") (pinfunction "2_2") (pintype "unspecified"))
    )
    (net (code "59") (name "unconnected-(U3-AIN3{slash}IOUT{slash}VBIAS{slash}P2-Pad11)") (class "Default")
      (node (ref "U3") (pin "11") (pinfunction "AIN3/IOUT/VBIAS/P2_11") (pintype "bidirectional"))
    )
    (net (code "60") (name "unconnected-(U3-AIN4{slash}IOUT{slash}VBIAS-Pad14)") (class "Default")
      (node (ref "U3") (pin "14") (pinfunction "AIN4/IOUT/VBIAS_14") (pintype "bidirectional"))
    )
    (net (code "61") (name "unconnected-(U3-AIN5{slash}IOUT{slash}VBIAS-Pad15)") (class "Default")
      (node (ref "U3") (pin "15") (pinfunction "AIN5/IOUT/VBIAS_15") (pintype "bidirectional"))
    )
    (net (code "62") (name "unconnected-(U3-AIN6{slash}IOUT{slash}VBIAS{slash}REFIN2+-Pad16)") (class "Default")
      (node (ref "U3") (pin "16") (pinfunction "AIN6/IOUT/VBIAS/REFIN2+_16") (pintype "bidirectional"))
    )
    (net (code "63") (name "unconnected-(U3-AIN7{slash}IOUT{slash}VBIAS{slash}REFIN2--Pad17)") (class "Default")
      (node (ref "U3") (pin "17") (pinfunction "AIN7/IOUT/VBIAS/REFIN2-_17") (pintype "bidirectional"))
    )
    (net (code "64") (name "unconnected-(U3-AVDD-Pad22)") (class "Default")
      (node (ref "U3") (pin "22") (pinfunction "AVDD_22") (pintype "unspecified"))
    )
    (net (code "65") (name "unconnected-(U3-CLK-Pad3)") (class "Default")
      (node (ref "U3") (pin "3") (pinfunction "CLK_3") (pintype "bidirectional"))
    )
    (net (code "66") (name "unconnected-(U3-PSW-Pad21)") (class "Default")
      (node (ref "U3") (pin "21") (pinfunction "PSW_21") (pintype "unspecified"))
    )
    (net (code "67") (name "unconnected-(U3-REFOUT-Pad18)") (class "Default")
      (node (ref "U3") (pin "18") (pinfunction "REFOUT_18") (pintype "output"))
    )
    (net (code "68") (name "unconnected-(U3-REGCAPA-Pad20)") (class "Default")
      (node (ref "U3") (pin "20") (pinfunction "REGCAPA_20") (pintype "output"))
    )
    (net (code "69") (name "unconnected-(U3-~SYNC~-Pad23)") (class "Default")
      (node (ref "U3") (pin "23") (pinfunction "~SYNC~_23") (pintype "input"))
    )
    (net (code "70") (name "unconnected-(U4-IO2-Pad3)") (class "Default")
      (node (ref "U4") (pin "3") (pinfunction "IO2_3") (pintype "bidirectional"))
    )
    (net (code "71") (name "unconnected-(U8-IN_2-Pad1)") (class "Default")
      (node (ref "U8") (pin "1") (pinfunction "IN_2_1") (pintype "input"))
    )
    (net (code "72") (name "unconnected-(U8-OUTS-Pad9)") (class "Default")
      (node (ref "U8") (pin "9") (pinfunction "OUTS_9") (pintype "output"))
    )
    (net (code "73") (name "unconnected-(U14-NC-Pad6*6)") (class "Default")
      (node (ref "U14") (pin "6*6") (pinfunction "NC_6*6") (pintype "unspecified"))
    )
    (net (code "74") (name "unconnected-(U14-SYNC_OK-Pad5)") (class "Default")
      (node (ref "U14") (pin "5") (pinfunction "SYNC_OK_5") (pintype "input"))
    )
    (net (code "75") (name "unconnected-(U18-NIC-Pad7)") (class "Default")
      (node (ref "U18") (pin "7") (pinfunction "NIC_7") (pintype "unspecified"))
    )
    (net (code "76") (name "unconnected-(U18-VE2-Pad10)") (class "Default")
      (node (ref "U18") (pin "10") (pinfunction "VE2_10") (pintype "unspecified"))
    )
    (net (code "77") (name "unconnected-(U22-IO2-Pad3)") (class "Default")
      (node (ref "U22") (pin "3") (pinfunction "IO2_3") (pintype "bidirectional"))
    )
    (net (code "78") (name "unconnected-(U31-IO2-Pad3)") (class "Default")
      (node (ref "U31") (pin "3") (pinfunction "IO2_3") (pintype "bidirectional"))
    )
    (net (code "79") (name "unconnected-(U50-INT1-Pad6)") (class "Default")
      (node (ref "U50") (pin "6") (pinfunction "INT1_6") (pintype "unspecified"))
    )
    (net (code "80") (name "unconnected-(U50-INT2-Pad5)") (class "Default")
      (node (ref "U50") (pin "5") (pinfunction "INT2_5") (pintype "unspecified"))
    )
    (net (code "81") (name "unconnected-(U51-3.3V_(250_M_A_MAX)-Pad53)") (class "Default")
      (node (ref "U51") (pin "53") (pinfunction "3.3V_(250_M_A_MAX)_53") (pintype "bidirectional"))
    )
    (net (code "82") (name "unconnected-(U51-A0-Pad14)") (class "Default")
      (node (ref "U51") (pin "14") (pinfunction "A0_14") (pintype "bidirectional"))
    )
    (net (code "83") (name "unconnected-(U51-A1-Pad15)") (class "Default")
      (node (ref "U51") (pin "15") (pinfunction "A1_15") (pintype "bidirectional"))
    )
    (net (code "84") (name "unconnected-(U51-A2-Pad16)") (class "Default")
      (node (ref "U51") (pin "16") (pinfunction "A2_16") (pintype "bidirectional"))
    )
    (net (code "85") (name "unconnected-(U51-A3-Pad17)") (class "Default")
      (node (ref "U51") (pin "17") (pinfunction "A3_17") (pintype "bidirectional"))
    )
    (net (code "86") (name "unconnected-(U51-A4-Pad18)") (class "Default")
      (node (ref "U51") (pin "18") (pinfunction "A4_18") (pintype "bidirectional"))
    )
    (net (code "87") (name "unconnected-(U51-A5-Pad19)") (class "Default")
      (node (ref "U51") (pin "19") (pinfunction "A5_19") (pintype "bidirectional"))
    )
    (net (code "88") (name "unconnected-(U51-A6-Pad20)") (class "Default")
      (node (ref "U51") (pin "20") (pinfunction "A6_20") (pintype "bidirectional"))
    )
    (net (code "89") (name "unconnected-(U51-A7-Pad21)") (class "Default")
      (node (ref "U51") (pin "21") (pinfunction "A7_21") (pintype "bidirectional"))
    )
    (net (code "90") (name "unconnected-(U51-A8-Pad22)") (class "Default")
      (node (ref "U51") (pin "22") (pinfunction "A8_22") (pintype "bidirectional"))
    )
    (net (code "91") (name "unconnected-(U51-A9-Pad23)") (class "Default")
      (node (ref "U51") (pin "23") (pinfunction "A9_23") (pintype "bidirectional"))
    )
    (net (code "92") (name "unconnected-(U51-A10-Pad24)") (class "Default")
      (node (ref "U51") (pin "24") (pinfunction "A10_24") (pintype "bidirectional"))
    )
    (net (code "93") (name "unconnected-(U51-A11-Pad25)") (class "Default")
      (node (ref "U51") (pin "25") (pinfunction "A11_25") (pintype "bidirectional"))
    )
    (net (code "94") (name "unconnected-(U51-A14-Pad38)") (class "Default")
      (node (ref "U51") (pin "38") (pinfunction "A14_38") (pintype "bidirectional"))
    )
    (net (code "95") (name "unconnected-(U51-A16-Pad40)") (class "Default")
      (node (ref "U51") (pin "40") (pinfunction "A16_40") (pintype "bidirectional"))
    )
    (net (code "96") (name "unconnected-(U51-A17-Pad41)") (class "Default")
      (node (ref "U51") (pin "41") (pinfunction "A17_41") (pintype "bidirectional"))
    )
    (net (code "97") (name "unconnected-(U51-BCLK2-Pad4)") (class "Default")
      (node (ref "U51") (pin "4") (pinfunction "BCLK2_4") (pintype "bidirectional"))
    )
    (net (code "98") (name "unconnected-(U51-CRX3-Pad30)") (class "Default")
      (node (ref "U51") (pin "30") (pinfunction "CRX3_30") (pintype "bidirectional"))
    )
    (net (code "99") (name "unconnected-(U51-CS_2-Pad36)") (class "Default")
      (node (ref "U51") (pin "36") (pinfunction "CS_2_36") (pintype "bidirectional"))
    )
    (net (code "100") (name "unconnected-(U51-CS_3-Pad37)") (class "Default")
      (node (ref "U51") (pin "37") (pinfunction "CS_3_37") (pintype "bidirectional"))
    )
    (net (code "101") (name "unconnected-(U51-CTX3-Pad31)") (class "Default")
      (node (ref "U51") (pin "31") (pinfunction "CTX3_31") (pintype "bidirectional"))
    )
    (net (code "102") (name "unconnected-(U51-D+-Pad50)") (class "Default")
      (node (ref "U51") (pin "50") (pinfunction "D+_50") (pintype "bidirectional"))
    )
    (net (code "103") (name "unconnected-(U51-D--Pad51)") (class "Default")
      (node (ref "U51") (pin "51") (pinfunction "D-_51") (pintype "bidirectional"))
    )
    (net (code "104") (name "unconnected-(U51-IN2-Pad5)") (class "Default")
      (node (ref "U51") (pin "5") (pinfunction "IN2_5") (pintype "bidirectional"))
    )
    (net (code "105") (name "unconnected-(U51-LRCLK2-Pad3)") (class "Default")
      (node (ref "U51") (pin "3") (pinfunction "LRCLK2_3") (pintype "bidirectional"))
    )
    (net (code "106") (name "unconnected-(U51-MCLK2-Pad33)") (class "Default")
      (node (ref "U51") (pin "33") (pinfunction "MCLK2_33") (pintype "bidirectional"))
    )
    (net (code "107") (name "unconnected-(U51-ON{slash}OFF-Pad47)") (class "Default")
      (node (ref "U51") (pin "47") (pinfunction "ON/OFF_47") (pintype "bidirectional"))
    )
    (net (code "108") (name "unconnected-(U51-OUT1B-Pad32)") (class "Default")
      (node (ref "U51") (pin "32") (pinfunction "OUT1B_32") (pintype "bidirectional"))
    )
    (net (code "109") (name "unconnected-(U51-OUT1C-Pad9)") (class "Default")
      (node (ref "U51") (pin "9") (pinfunction "OUT1C_9") (pintype "bidirectional"))
    )
    (net (code "110") (name "unconnected-(U51-OUT1D-Pad6)") (class "Default")
      (node (ref "U51") (pin "6") (pinfunction "OUT1D_6") (pintype "bidirectional"))
    )
    (net (code "111") (name "unconnected-(U51-OUT2-Pad2)") (class "Default")
      (node (ref "U51") (pin "2") (pinfunction "OUT2_2") (pintype "bidirectional"))
    )
    (net (code "112") (name "unconnected-(U51-PROGRAM-Pad46)") (class "Default")
      (node (ref "U51") (pin "46") (pinfunction "PROGRAM_46") (pintype "bidirectional"))
    )
    (net (code "113") (name "unconnected-(U51-RX1-Pad57)") (class "Default")
      (node (ref "U51") (pin "57") (pinfunction "RX1_57") (pintype "bidirectional"))
    )
    (net (code "114") (name "unconnected-(U51-RX2-Pad7)") (class "Default")
      (node (ref "U51") (pin "7") (pinfunction "RX2_7") (pintype "bidirectional"))
    )
    (net (code "115") (name "unconnected-(U51-RX8-Pad34)") (class "Default")
      (node (ref "U51") (pin "34") (pinfunction "RX8_34") (pintype "bidirectional"))
    )
    (net (code "116") (name "unconnected-(U51-TX1-Pad1)") (class "Default")
      (node (ref "U51") (pin "1") (pinfunction "TX1_1") (pintype "bidirectional"))
    )
    (net (code "117") (name "unconnected-(U51-TX2-Pad8)") (class "Default")
      (node (ref "U51") (pin "8") (pinfunction "TX2_8") (pintype "bidirectional"))
    )
    (net (code "118") (name "unconnected-(U51-TX7-Pad29)") (class "Default")
      (node (ref "U51") (pin "29") (pinfunction "TX7_29") (pintype "bidirectional"))
    )
    (net (code "119") (name "unconnected-(U51-TX8-Pad35)") (class "Default")
      (node (ref "U51") (pin "35") (pinfunction "TX8_35") (pintype "bidirectional"))
    )
    (net (code "120") (name "unconnected-(U51-VBAT-Pad43)") (class "Default")
      (node (ref "U51") (pin "43") (pinfunction "VBAT_43") (pintype "bidirectional"))
    )
    (net (code "121") (name "unconnected-(U51-VUSB-Pad68)") (class "Default")
      (node (ref "U51") (pin "68") (pinfunction "VUSB_68") (pintype "bidirectional"))
    )
  )
)
